# AS5147.net
KiCad netlist of a schematic drawn in Altium Designer
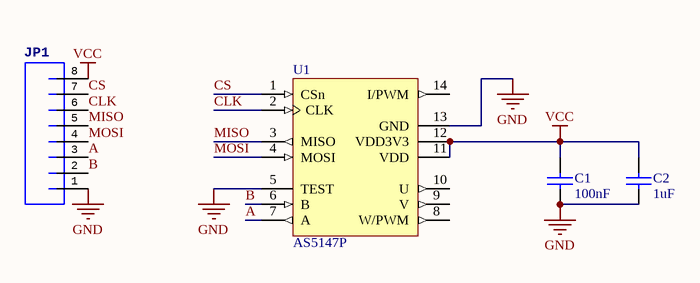
[diagram p0: AS5147.SchDoc]

(export (version "E")
  (design (tool "Eeschema 10.0.6"))
  (components
    (comp (ref "C1")
      (value "100nF")
      (footprint "CAPC0402(1005)60_L")
      (description "CAP 100nF 6.3V ±5% 0402 (1005 Metric) Thickness 0.6mm SMD")
      (fields (field (name "TOLERANCE") "Â±5%"))
      (libsource (lib "Altium Content Vault") (part "CMP-1034-02060-1"))
    )
    (comp (ref "C2")
      (value "1uF")
      (footprint "CAPC0402(1005)60_L")
      (description "CAP 1uF 6.3V ±10% 0402 (1005 Metric) Thickness 0.6mm SMD")
      (fields (field (name "TOLERANCE") "Â±10%"))
      (libsource (lib "Altium Content Vault") (part "CMP-1034-02113-1"))
    )
    (comp (ref "JP1") (value "~") (footprint "JST-8-SMD") (libsource (lib "Components") (part "JST_8_VERT")))
    (comp (ref "U1")
      (value "AS5147P")
      (footprint "AMS-TSSOP-14-5000X4400DE_N")
      (libsource (lib "Components") (part "AMS-AS5147P"))
    )
  )
  (nets
    (net (code "1") (name "/A") (class "Default")
      (node (ref "JP1") (pin "3") (pinfunction "3_3") (pintype "passive"))
      (node (ref "U1") (pin "7") (pinfunction "A_7") (pintype "output"))
    )
    (net (code "2") (name "/B") (class "Default")
      (node (ref "JP1") (pin "2") (pinfunction "2_2") (pintype "passive"))
      (node (ref "U1") (pin "6") (pinfunction "B_6") (pintype "input"))
    )
    (net (code "3") (name "/CLK") (class "Default")
      (node (ref "JP1") (pin "6") (pinfunction "6_6") (pintype "passive"))
      (node (ref "U1") (pin "2") (pinfunction "CLK_2") (pintype "input"))
    )
    (net (code "4") (name "/CS") (class "Default")
      (node (ref "JP1") (pin "7") (pinfunction "7_7") (pintype "passive"))
      (node (ref "U1") (pin "1") (pinfunction "CSn_1") (pintype "input"))
    )
    (net (code "5") (name "/MISO") (class "Default")
      (node (ref "JP1") (pin "5") (pinfunction "5_5") (pintype "passive"))
      (node (ref "U1") (pin "3") (pinfunction "MISO_3") (pintype "output"))
    )
    (net (code "6") (name "/MOSI") (class "Default")
      (node (ref "JP1") (pin "4") (pinfunction "4_4") (pintype "passive"))
      (node (ref "U1") (pin "4") (pinfunction "MOSI_4") (pintype "input"))
    )
    (net (code "7") (name "GND") (class "Default")
      (node (ref "C1") (pin "1") (pinfunction "1_1") (pintype "passive"))
      (node (ref "C2") (pin "1") (pinfunction "1_1") (pintype "passive"))
      (node (ref "JP1") (pin "1") (pinfunction "1_1") (pintype "passive"))
      (node (ref "U1") (pin "13") (pinfunction "GND_13") (pintype "power_in"))
      (node (ref "U1") (pin "5") (pinfunction "TEST_5") (pintype "passive"))
    )
    (net (code "8") (name "VCC") (class "Default")
      (node (ref "C1") (pin "2") (pinfunction "2_2") (pintype "passive"))
      (node (ref "C2") (pin "2") (pinfunction "2_2") (pintype "passive"))
      (node (ref "JP1") (pin "8") (pinfunction "8_8") (pintype "passive"))
      (node (ref "U1") (pin "11") (pinfunction "VDD_11") (pintype "power_in"))
      (node (ref "U1") (pin "12") (pinfunction "VDD3V3_12") (pintype "power_in"))
    )
    (net (code "9") (name "unconnected-(U1-I{slash}PWM-Pad14)") (class "Default")
      (node (ref "U1") (pin "14") (pinfunction "I/PWM_14") (pintype "output"))
    )
    (net (code "10") (name "unconnected-(U1-U-Pad10)") (class "Default")
      (node (ref "U1") (pin "10") (pinfunction "U_10") (pintype "output"))
    )
    (net (code "11") (name "unconnected-(U1-V-Pad9)") (class "Default")
      (node (ref "U1") (pin "9") (pinfunction "V_9") (pintype "output"))
    )
    (net (code "12") (name "unconnected-(U1-W{slash}PWM-Pad8)") (class "Default")
      (node (ref "U1") (pin "8") (pinfunction "W/PWM_8") (pintype "output"))
    )
  )
)
